# SCH_Power-Controller.net
KiCad netlist of a schematic drawn in EasyEDA
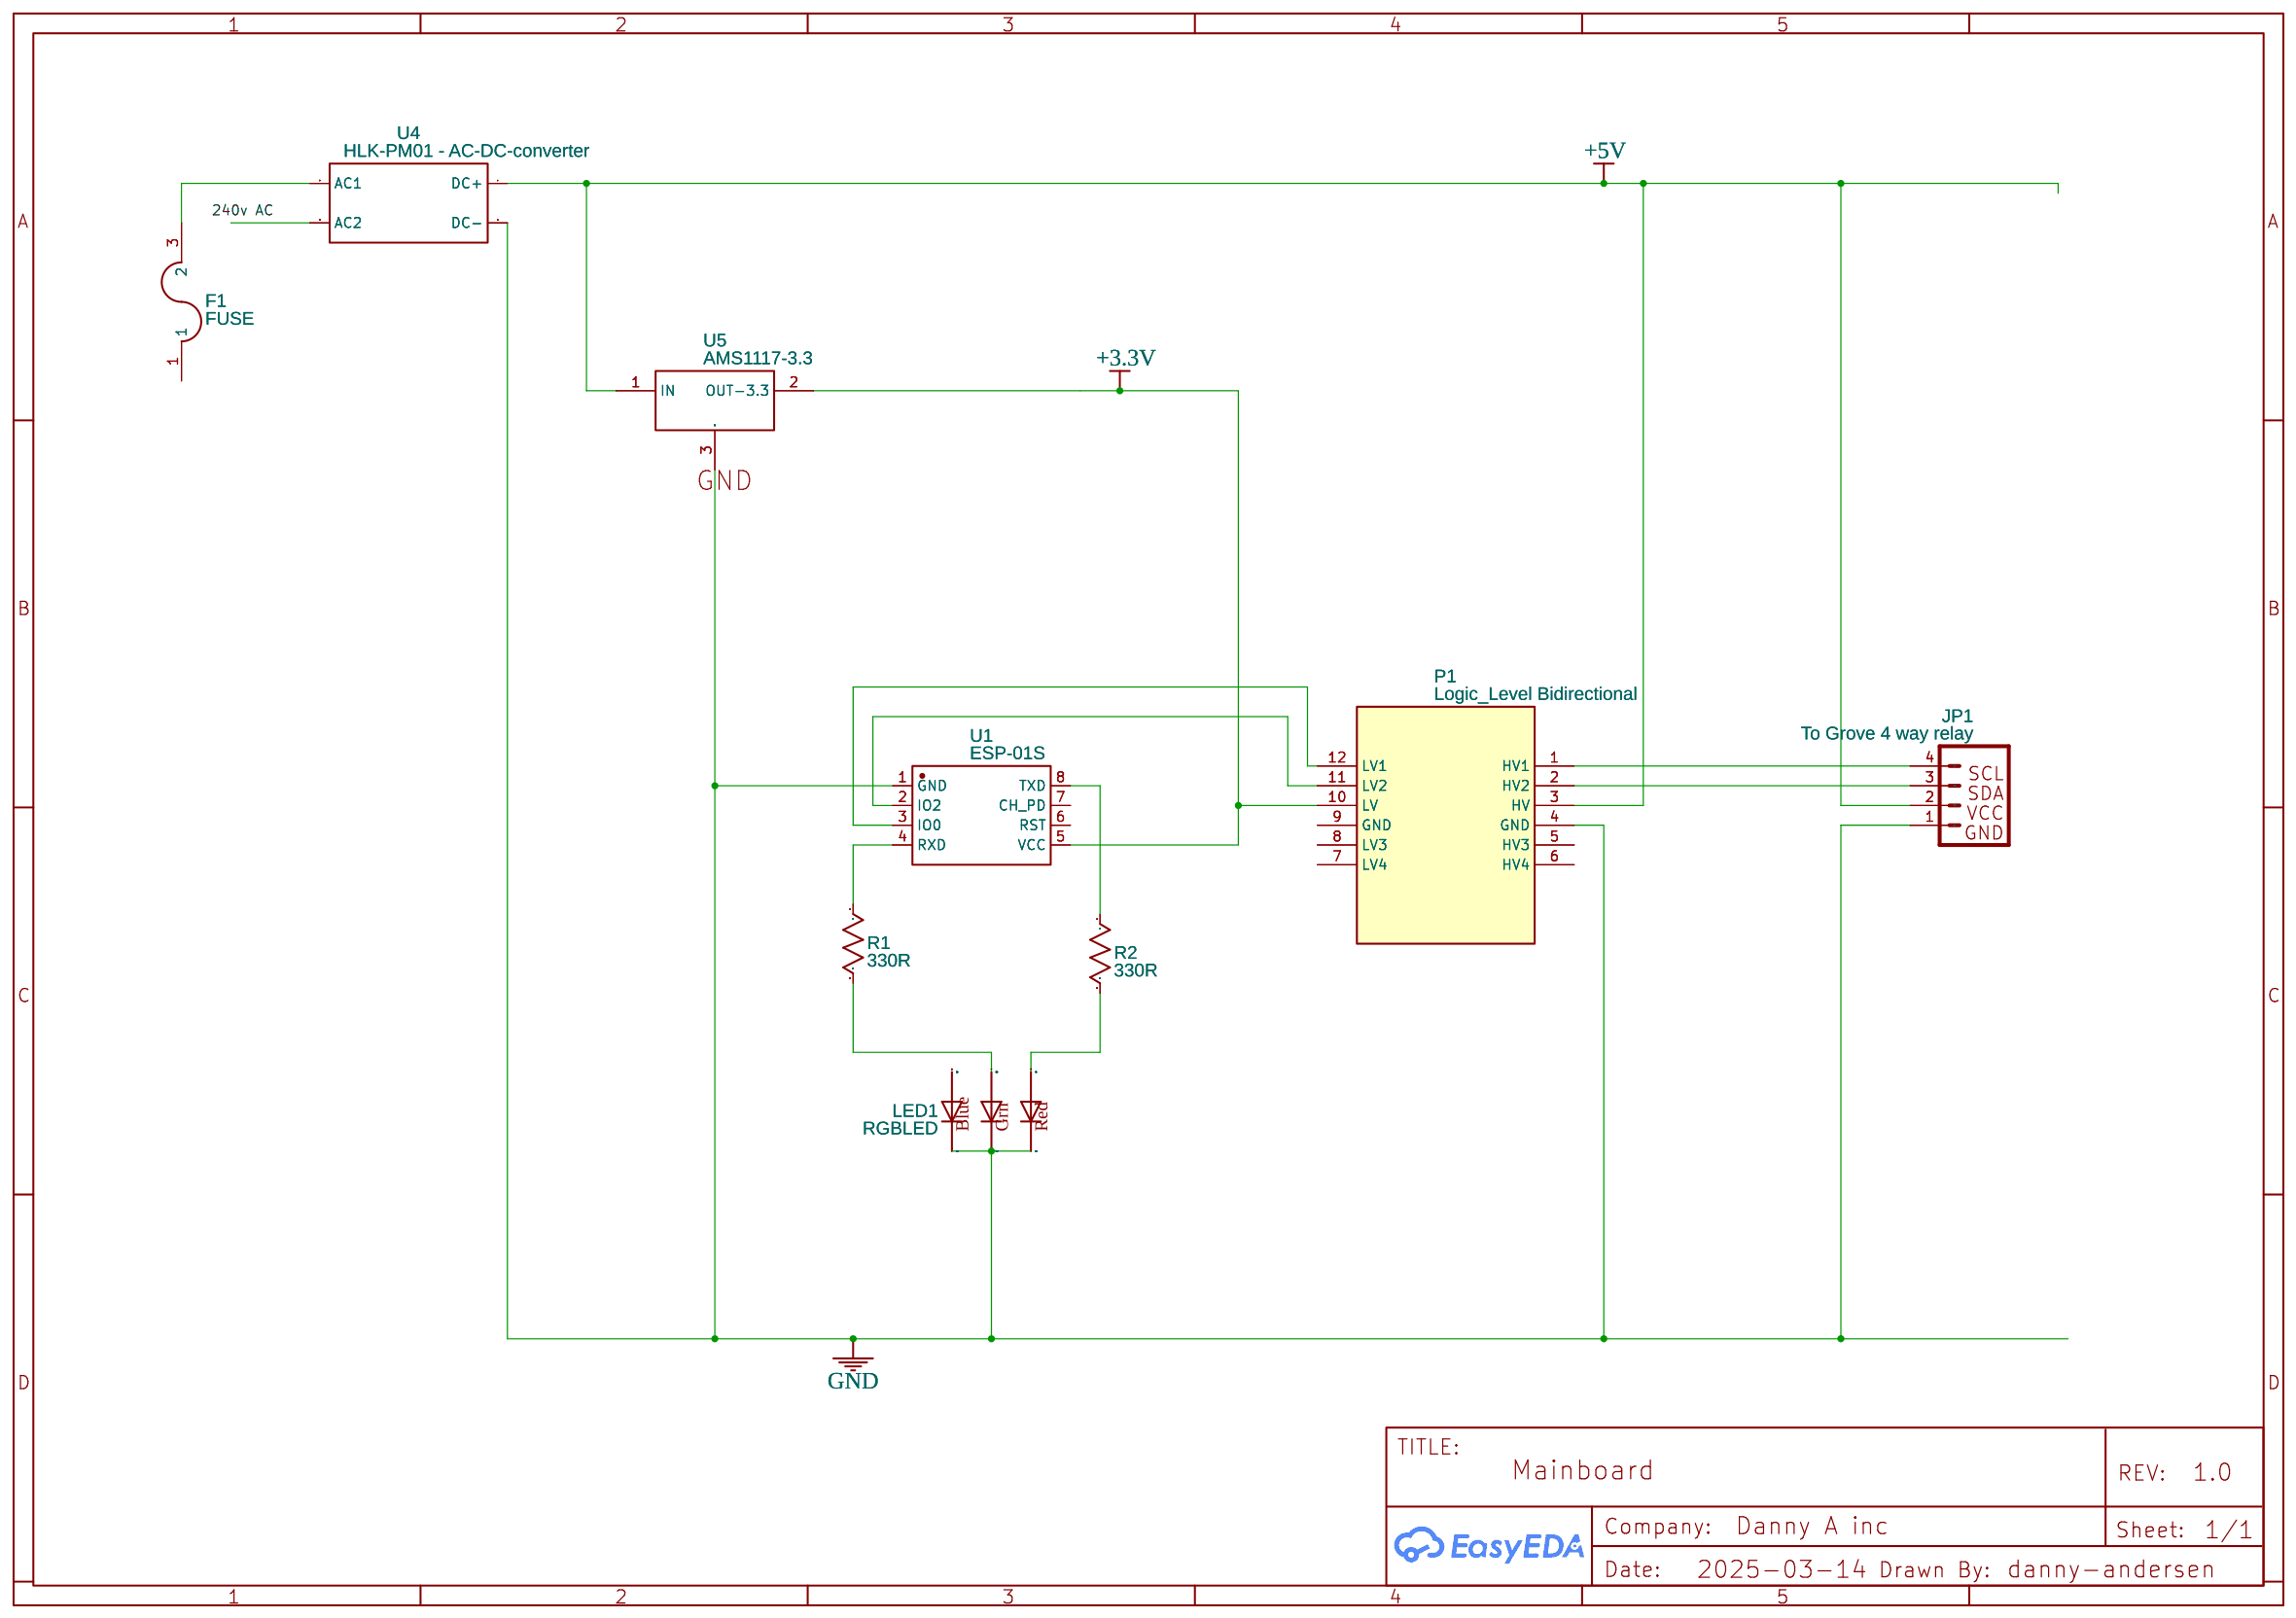
[diagram p0: schematic sheet]

(export (version "E")
  (design (tool "Eeschema 10.0.6"))
  (components
    (comp (ref "F1")
      (value "FUSE")
      (fields (field (name "Manufacturer Part") "?"))
      (libsource (lib "") (part "Unknown_85_-660"))
    )
    (comp (ref "JP1") (value "To Grove 4 way relay") (libsource (lib "") (part "I2C_STANDARD")))
    (comp (ref "LED1") (value "RGBLED") (libsource (lib "") (part "RGBLED")))
    (comp (ref "P1")
      (value "Logic_Level Bidirectional")
      (libsource (lib "") (part "Logic_Level Bidirectional"))
    )
    (comp (ref "R1") (value "330R") (libsource (lib "") (part "R_0603_US")))
    (comp (ref "R2") (value "330R") (libsource (lib "") (part "R_0603_US")))
    (comp (ref "U1")
      (value "ESP-01S")
      (fields (field (name "Manufacturer") "Ai-Thinker"))
      (libsource (lib "") (part "ESP-01S"))
    )
    (comp (ref "U4")
      (value "HLK-PM01 - AC-DC-converter")
      (fields (field (name "Manufacturer Part") "?"))
      (libsource (lib "") (part "Unknown_190_-710"))
    )
    (comp (ref "U5")
      (value "AMS1117-3.3")
      (fields (field (name "Manufacturer Part") "CJ78L05") (field (name "Manufacturer") "CJ"))
      (libsource (lib "") (part "7805(SOT-89)"))
    )
  )
  (nets
    (net (code "1") (name "+3.3V") (class "Default")
      (node (ref "P1") (pin "10") (pinfunction "LV_10") (pintype "unspecified"))
      (node (ref "U1") (pin "5") (pinfunction "VCC_5") (pintype "unspecified"))
      (node (ref "U5") (pin "2") (pinfunction "OUT-3.3_2") (pintype "passive"))
    )
    (net (code "2") (name "+5V") (class "Default")
      (node (ref "JP1") (pin "2") (pinfunction "2_2") (pintype "unspecified"))
      (node (ref "P1") (pin "3") (pinfunction "HV_3") (pintype "unspecified"))
      (node (ref "U4") (pin "4") (pinfunction "DC+_4") (pintype "unspecified"))
      (node (ref "U5") (pin "1") (pinfunction "IN_1") (pintype "passive"))
    )
    (net (code "4") (name "GND") (class "Default")
      (node (ref "JP1") (pin "1") (pinfunction "1_1") (pintype "unspecified"))
      (node (ref "LED1") (pin "4") (pinfunction "BLUE_C_4") (pintype "unspecified"))
      (node (ref "LED1") (pin "5") (pinfunction "RED_C_5") (pintype "unspecified"))
      (node (ref "LED1") (pin "6") (pinfunction "GREEN_C_6") (pintype "unspecified"))
      (node (ref "P1") (pin "4") (pinfunction "GND_4") (pintype "unspecified"))
      (node (ref "U1") (pin "1") (pinfunction "GND_1") (pintype "unspecified"))
      (node (ref "U4") (pin "3") (pinfunction "DC-_3") (pintype "unspecified"))
      (node (ref "U5") (pin "3") (pinfunction "GND_3") (pintype "passive"))
    )
    (net (code "5") (name "Net-(F1-2)") (class "Default")
      (node (ref "F1") (pin "3") (pinfunction "2_3") (pintype "unspecified"))
      (node (ref "U4") (pin "1") (pinfunction "AC1_1") (pintype "input"))
    )
    (net (code "6") (name "Net-(LED1-GREEN_A)") (class "Default")
      (node (ref "LED1") (pin "1") (pinfunction "GREEN_A_1") (pintype "unspecified"))
      (node (ref "R1") (pin "2") (pinfunction "2_2") (pintype "unspecified"))
    )
    (net (code "7") (name "Net-(LED1-RED_A)") (class "Default")
      (node (ref "LED1") (pin "2") (pinfunction "RED_A_2") (pintype "unspecified"))
      (node (ref "R2") (pin "2") (pinfunction "2_2") (pintype "unspecified"))
    )
    (net (code "8") (name "Net-(P1-HV1)") (class "Default")
      (node (ref "JP1") (pin "4") (pinfunction "4_4") (pintype "unspecified"))
      (node (ref "P1") (pin "1") (pinfunction "HV1_1") (pintype "unspecified"))
    )
    (net (code "9") (name "Net-(P1-HV2)") (class "Default")
      (node (ref "JP1") (pin "3") (pinfunction "3_3") (pintype "unspecified"))
      (node (ref "P1") (pin "2") (pinfunction "HV2_2") (pintype "unspecified"))
    )
    (net (code "10") (name "Net-(P1-LV1)") (class "Default")
      (node (ref "P1") (pin "12") (pinfunction "LV1_12") (pintype "unspecified"))
      (node (ref "U1") (pin "3") (pinfunction "IO0_3") (pintype "unspecified"))
    )
    (net (code "11") (name "Net-(P1-LV2)") (class "Default")
      (node (ref "P1") (pin "11") (pinfunction "LV2_11") (pintype "unspecified"))
      (node (ref "U1") (pin "2") (pinfunction "IO2_2") (pintype "unspecified"))
    )
    (net (code "12") (name "Net-(U1-RXD)") (class "Default")
      (node (ref "R1") (pin "1") (pinfunction "1_1") (pintype "unspecified"))
      (node (ref "U1") (pin "4") (pinfunction "RXD_4") (pintype "unspecified"))
    )
    (net (code "13") (name "Net-(U1-TXD)") (class "Default")
      (node (ref "R2") (pin "1") (pinfunction "1_1") (pintype "unspecified"))
      (node (ref "U1") (pin "8") (pinfunction "TXD_8") (pintype "unspecified"))
    )
    (net (code "14") (name "unconnected-(F1-Pad1)") (class "Default")
      (node (ref "F1") (pin "1") (pinfunction "1_1") (pintype "unspecified"))
    )
    (net (code "15") (name "unconnected-(LED1-BLUE_A-Pad3)") (class "Default")
      (node (ref "LED1") (pin "3") (pinfunction "BLUE_A_3") (pintype "unspecified"))
    )
    (net (code "16") (name "unconnected-(P1-GND-Pad9)") (class "Default")
      (node (ref "P1") (pin "9") (pinfunction "GND_9") (pintype "unspecified"))
    )
    (net (code "17") (name "unconnected-(P1-HV3-Pad5)") (class "Default")
      (node (ref "P1") (pin "5") (pinfunction "HV3_5") (pintype "unspecified"))
    )
    (net (code "18") (name "unconnected-(P1-HV4-Pad6)") (class "Default")
      (node (ref "P1") (pin "6") (pinfunction "HV4_6") (pintype "unspecified"))
    )
    (net (code "19") (name "unconnected-(P1-LV3-Pad8)") (class "Default")
      (node (ref "P1") (pin "8") (pinfunction "LV3_8") (pintype "unspecified"))
    )
    (net (code "20") (name "unconnected-(P1-LV4-Pad7)") (class "Default")
      (node (ref "P1") (pin "7") (pinfunction "LV4_7") (pintype "unspecified"))
    )
    (net (code "21") (name "unconnected-(U1-CH_PD-Pad7)") (class "Default")
      (node (ref "U1") (pin "7") (pinfunction "CH_PD_7") (pintype "unspecified"))
    )
    (net (code "22") (name "unconnected-(U1-RST-Pad6)") (class "Default")
      (node (ref "U1") (pin "6") (pinfunction "RST_6") (pintype "unspecified"))
    )
    (net (code "23") (name "unconnected-(U4-AC2-Pad2)") (class "Default")
      (node (ref "U4") (pin "2") (pinfunction "AC2_2") (pintype "input"))
    )
  )
)
